# FPGA_programmer.net
KiCad netlist of a schematic drawn in Altium Designer
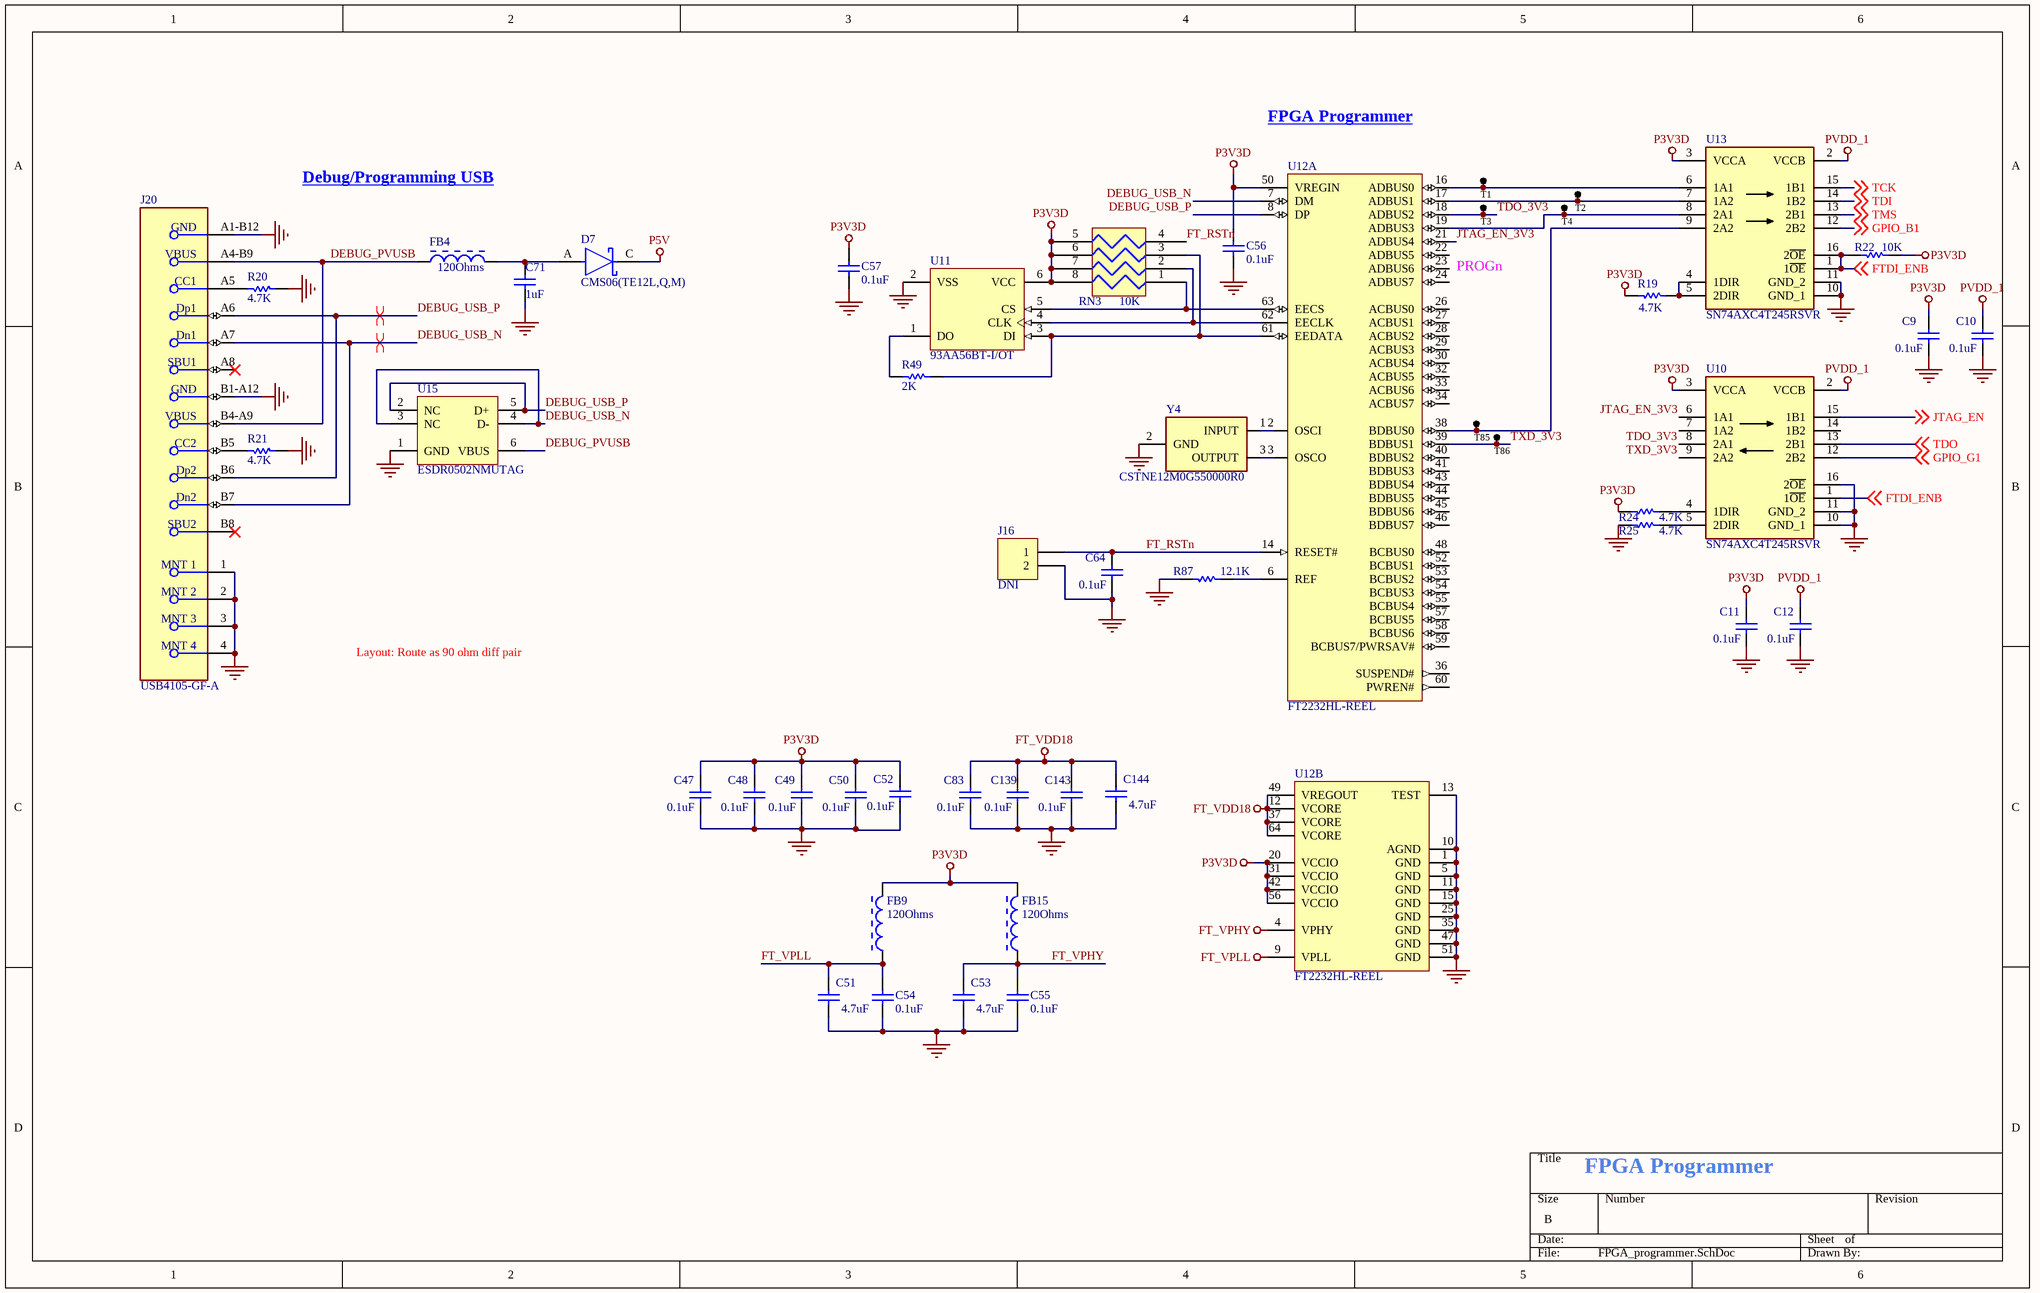
[diagram p0: FPGA_programmer.SchDoc]

(export (version "E")
  (design (tool "Eeschema 10.0.6"))
  (components
    (comp (ref "C9")
      (value "0.1uF")
      (footprint "CAPC1005X55USR")
      (description "CAP CER 0.1UF 16V X7R 0402")
      (fields
        (field (name "MANUFACTURER PART NUMBER") "CGA2B1X7R1C104K050BC")
        (field (name "MANUFACTURER") "TDK Corporation")
      )
      (libsource (lib "NX Module baseboard") (part "CAP CER 0.1UF 16V X7R 0402"))
    )
    (comp (ref "C10")
      (value "0.1uF")
      (footprint "CAPC1005X55USR")
      (description "CAP CER 0.1UF 16V X7R 0402")
      (fields
        (field (name "MANUFACTURER PART NUMBER") "CGA2B1X7R1C104K050BC")
        (field (name "MANUFACTURER") "TDK Corporation")
      )
      (libsource (lib "NX Module baseboard") (part "CAP CER 0.1UF 16V X7R 0402"))
    )
    (comp (ref "C11")
      (value "0.1uF")
      (footprint "CAPC1005X55USR")
      (description "CAP CER 0.1UF 16V X7R 0402")
      (fields
        (field (name "MANUFACTURER PART NUMBER") "CGA2B1X7R1C104K050BC")
        (field (name "MANUFACTURER") "TDK Corporation")
      )
      (libsource (lib "NX Module baseboard") (part "CAP CER 0.1UF 16V X7R 0402"))
    )
    (comp (ref "C12")
      (value "0.1uF")
      (footprint "CAPC1005X55USR")
      (description "CAP CER 0.1UF 16V X7R 0402")
      (fields
        (field (name "MANUFACTURER PART NUMBER") "CGA2B1X7R1C104K050BC")
        (field (name "MANUFACTURER") "TDK Corporation")
      )
      (libsource (lib "NX Module baseboard") (part "CAP CER 0.1UF 16V X7R 0402"))
    )
    (comp (ref "C47")
      (value "0.1uF")
      (footprint "CAPC1005X55USR")
      (description "CAP CER 0.1UF 16V X7R 0402")
      (fields
        (field (name "MANUFACTURER PART NUMBER") "CGA2B1X7R1C104K050BC")
        (field (name "MANUFACTURER") "TDK Corporation")
      )
      (libsource (lib "NX Module baseboard") (part "CAP CER 0.1UF 16V X7R 0402"))
    )
    (comp (ref "C48")
      (value "0.1uF")
      (footprint "CAPC1005X55USR")
      (description "CAP CER 0.1UF 16V X7R 0402")
      (fields
        (field (name "MANUFACTURER PART NUMBER") "CGA2B1X7R1C104K050BC")
        (field (name "MANUFACTURER") "TDK Corporation")
      )
      (libsource (lib "NX Module baseboard") (part "CAP CER 0.1UF 16V X7R 0402"))
    )
    (comp (ref "C49")
      (value "0.1uF")
      (footprint "CAPC1005X55USR")
      (description "CAP CER 0.1UF 16V X7R 0402")
      (fields
        (field (name "MANUFACTURER PART NUMBER") "CGA2B1X7R1C104K050BC")
        (field (name "MANUFACTURER") "TDK Corporation")
      )
      (libsource (lib "NX Module baseboard") (part "CAP CER 0.1UF 16V X7R 0402"))
    )
    (comp (ref "C50")
      (value "0.1uF")
      (footprint "CAPC1005X55USR")
      (description "CAP CER 0.1UF 16V X7R 0402")
      (fields
        (field (name "MANUFACTURER PART NUMBER") "CGA2B1X7R1C104K050BC")
        (field (name "MANUFACTURER") "TDK Corporation")
      )
      (libsource (lib "NX Module baseboard") (part "CAP CER 0.1UF 16V X7R 0402"))
    )
    (comp (ref "C51")
      (value "4.7uF")
      (footprint "CAPC1005X55USR")
      (description "CAP CER 4.7UF 10V X5R 0402")
      (fields
        (field (name "MANUFACTURER PART NUMBER") "C1005X5R1A475M050BC")
        (field (name "MANUFACTURER") "TDK Corporation")
      )
      (libsource (lib "NX Module baseboard") (part "CAP CER 4.7UF 10V X5R 0402"))
    )
    (comp (ref "C52")
      (value "0.1uF")
      (footprint "CAPC1005X55USR")
      (description "CAP CER 0.1UF 16V X7R 0402")
      (fields
        (field (name "MANUFACTURER PART NUMBER") "CGA2B1X7R1C104K050BC")
        (field (name "MANUFACTURER") "TDK Corporation")
      )
      (libsource (lib "NX Module baseboard") (part "CAP CER 0.1UF 16V X7R 0402"))
    )
    (comp (ref "C53")
      (value "4.7uF")
      (footprint "CAPC1005X55USR")
      (description "CAP CER 4.7UF 10V X5R 0402")
      (fields
        (field (name "MANUFACTURER PART NUMBER") "C1005X5R1A475M050BC")
        (field (name "MANUFACTURER") "TDK Corporation")
      )
      (libsource (lib "NX Module baseboard") (part "CAP CER 4.7UF 10V X5R 0402"))
    )
    (comp (ref "C54")
      (value "0.1uF")
      (footprint "CAPC1005X55USR")
      (description "CAP CER 0.1UF 16V X7R 0402")
      (fields
        (field (name "MANUFACTURER PART NUMBER") "CGA2B1X7R1C104K050BC")
        (field (name "MANUFACTURER") "TDK Corporation")
      )
      (libsource (lib "NX Module baseboard") (part "CAP CER 0.1UF 16V X7R 0402"))
    )
    (comp (ref "C55")
      (value "0.1uF")
      (footprint "CAPC1005X55USR")
      (description "CAP CER 0.1UF 16V X7R 0402")
      (fields
        (field (name "MANUFACTURER PART NUMBER") "CGA2B1X7R1C104K050BC")
        (field (name "MANUFACTURER") "TDK Corporation")
      )
      (libsource (lib "NX Module baseboard") (part "CAP CER 0.1UF 16V X7R 0402"))
    )
    (comp (ref "C56")
      (value "0.1uF")
      (footprint "CAPC1005X55USR")
      (description "CAP CER 0.1UF 16V X7R 0402")
      (fields
        (field (name "MANUFACTURER PART NUMBER") "CGA2B1X7R1C104K050BC")
        (field (name "MANUFACTURER") "TDK Corporation")
      )
      (libsource (lib "NX Module baseboard") (part "CAP CER 0.1UF 16V X7R 0402"))
    )
    (comp (ref "C57")
      (value "0.1uF")
      (footprint "CAPC1005X55USR")
      (description "CAP CER 0.1UF 16V X7R 0402")
      (fields
        (field (name "MANUFACTURER PART NUMBER") "CGA2B1X7R1C104K050BC")
        (field (name "MANUFACTURER") "TDK Corporation")
      )
      (libsource (lib "NX Module baseboard") (part "CAP CER 0.1UF 16V X7R 0402"))
    )
    (comp (ref "C64")
      (value "0.1uF")
      (footprint "CAPC1005X55USR")
      (description "CAP CER 0.1UF 16V X7R 0402")
      (fields
        (field (name "MANUFACTURER PART NUMBER") "CGA2B1X7R1C104K050BC")
        (field (name "MANUFACTURER") "TDK Corporation")
      )
      (libsource (lib "NX Module baseboard") (part "CAP CER 0.1UF 16V X7R 0402"))
    )
    (comp (ref "C71")
      (value "1uF")
      (footprint "CAPC1005X55USR")
      (description "CAP CER 1UF 25V X5R 0402")
      (fields
        (field (name "MANUFACTURER PART NUMBER") "GRM155R61E105MA12D")
        (field (name "MANUFACTURER") "Murata Electronics")
      )
      (libsource (lib "Tiger_Ti180") (part "CAP CER 1UF 25V X5R 0402"))
    )
    (comp (ref "C83")
      (value "0.1uF")
      (footprint "CAPC1005X55USR")
      (description "CAP CER 0.1UF 16V X7R 0402")
      (fields
        (field (name "MANUFACTURER PART NUMBER") "CGA2B1X7R1C104K050BC")
        (field (name "MANUFACTURER") "TDK Corporation")
      )
      (libsource (lib "NX Module baseboard") (part "CAP CER 0.1UF 16V X7R 0402"))
    )
    (comp (ref "C139")
      (value "0.1uF")
      (footprint "CAPC1005X55USR")
      (description "CAP CER 0.1UF 16V X7R 0402")
      (fields
        (field (name "MANUFACTURER PART NUMBER") "CGA2B1X7R1C104K050BC")
        (field (name "MANUFACTURER") "TDK Corporation")
      )
      (libsource (lib "NX Module baseboard") (part "CAP CER 0.1UF 16V X7R 0402"))
    )
    (comp (ref "C143")
      (value "0.1uF")
      (footprint "CAPC1005X55USR")
      (description "CAP CER 0.1UF 16V X7R 0402")
      (fields
        (field (name "MANUFACTURER PART NUMBER") "CGA2B1X7R1C104K050BC")
        (field (name "MANUFACTURER") "TDK Corporation")
      )
      (libsource (lib "NX Module baseboard") (part "CAP CER 0.1UF 16V X7R 0402"))
    )
    (comp (ref "C144")
      (value "4.7uF")
      (footprint "CAPC1005X55USR")
      (description "CAP CER 4.7UF 10V X5R 0402")
      (fields
        (field (name "MANUFACTURER PART NUMBER") "C1005X5R1A475M050BC")
        (field (name "MANUFACTURER") "TDK Corporation")
      )
      (libsource (lib "NX Module baseboard") (part "CAP CER 4.7UF 10V X5R 0402"))
    )
    (comp (ref "D7")
      (value "CMS06(TE12L,Q,M)")
      (footprint "SOD-128")
      (description "Rectifier Diode Schottky 30V 2A 2-Pin M-FLAT T/R")
      (fields (field (name "MANUFACTURER") "Toshiba"))
      (libsource (lib "Tiger_Ti180") (part "D_CMS06(TE12L,Q,M)"))
    )
    (comp (ref "FB4")
      (value "120Ohms")
      (footprint "0402_FB")
      (description "FERRITE BEAD 120 OHM 0402 1LN")
      (fields
        (field (name "MANUFACTURER PART NUMBER") "BLM15AG121SN1D")
        (field (name "MANUFACTURER") "Murata Electronics")
      )
      (libsource (lib "AiC") (part "FERRITE BEAD 120 OHM 0402 1LN"))
    )
    (comp (ref "FB9")
      (value "120Ohms")
      (footprint "0402_FB")
      (description "FERRITE BEAD 120 OHM 0402 1LN")
      (fields
        (field (name "MANUFACTURER PART NUMBER") "BLM15AG121SN1D")
        (field (name "MANUFACTURER") "Murata Electronics")
      )
      (libsource (lib "AiC") (part "FERRITE BEAD 120 OHM 0402 1LN"))
    )
    (comp (ref "FB15")
      (value "120Ohms")
      (footprint "0402_FB")
      (description "FERRITE BEAD 120 OHM 0402 1LN")
      (fields
        (field (name "MANUFACTURER PART NUMBER") "BLM15AG121SN1D")
        (field (name "MANUFACTURER") "Murata Electronics")
      )
      (libsource (lib "AiC") (part "FERRITE BEAD 120 OHM 0402 1LN"))
    )
    (comp (ref "J16")
      (value "Header 2X1_2.54MM")
      (footprint "HDR2X1_MALE_2.54MM")
      (description "Conn Header Vert 2POS 2.54MM")
      (fields
        (field (name "MANUFACTURER PART NUMBER") "PRPC002SAAN-RC")
        (field (name "MANUFACTURER") "Sullins")
        (field (name "CONTENT") "DNI")
      )
      (libsource (lib "NX Module baseboard") (part "Header 2X1_2.54MM"))
    )
    (comp (ref "J20")
      (value "USB4105-GF-A")
      (footprint "USB4105_GCT")
      (description "Conn USB 2.0 Type C RCP 24 POS 0.3mm/0.5mm Solder RA SMD 24 Terminal 1 Port T/R")
      (fields (field (name "MANUFACTURER") "Global Connector Technology"))
      (libsource (lib "Tiger_Ti180") (part "CONN RCP USB2.0 TYP C 24P SMD RA"))
    )
    (comp (ref "R19")
      (value "4.7K")
      (footprint "RESC1005X40USR")
      (description "RES SMD 4.7K OHM 1% 1/16W 0402")
      (fields
        (field (name "MANUFACTURER") "Stackpole Electronics Inc")
        (field (name "MANUFACTURER PART NUMBER") "RMCF0402FT4K70")
      )
      (libsource (lib "Tiger_Ti180") (part "RES 4.7K OHM 1% 1/16W 0402"))
    )
    (comp (ref "R20")
      (value "4.7K")
      (footprint "RESC1005X40USR")
      (description "RES SMD 4.7K OHM 1% 1/16W 0402")
      (fields
        (field (name "MANUFACTURER") "Stackpole Electronics Inc")
        (field (name "MANUFACTURER PART NUMBER") "RMCF0402FT4K70")
      )
      (libsource (lib "Tiger_Ti180") (part "RES 4.7K OHM 1% 1/16W 0402"))
    )
    (comp (ref "R21")
      (value "4.7K")
      (footprint "RESC1005X40USR")
      (description "RES SMD 4.7K OHM 1% 1/16W 0402")
      (fields
        (field (name "MANUFACTURER") "Stackpole Electronics Inc")
        (field (name "MANUFACTURER PART NUMBER") "RMCF0402FT4K70")
      )
      (libsource (lib "Tiger_Ti180") (part "RES 4.7K OHM 1% 1/16W 0402"))
    )
    (comp (ref "R22")
      (value "10K")
      (footprint "RESC1005X40USR")
      (description "RES SMD 10K OHM 1% 1/16W 0402")
      (fields
        (field (name "MANUFACTURER") "Samsung Electro-Mechanics")
        (field (name "MANUFACTURER PART NUMBER") "RC1005F103CS")
      )
      (libsource (lib "NX Module baseboard") (part "RES SMD 10K OHM 1% 1/16W 0402"))
    )
    (comp (ref "R24")
      (value "4.7K")
      (footprint "RESC1005X40USR")
      (description "RES SMD 4.7K OHM 1% 1/16W 0402")
      (fields
        (field (name "MANUFACTURER") "Stackpole Electronics Inc")
        (field (name "MANUFACTURER PART NUMBER") "RMCF0402FT4K70")
      )
      (libsource (lib "Tiger_Ti180") (part "RES 4.7K OHM 1% 1/16W 0402"))
    )
    (comp (ref "R25")
      (value "4.7K")
      (footprint "RESC1005X40USR")
      (description "RES SMD 4.7K OHM 1% 1/16W 0402")
      (fields
        (field (name "MANUFACTURER") "Stackpole Electronics Inc")
        (field (name "MANUFACTURER PART NUMBER") "RMCF0402FT4K70")
      )
      (libsource (lib "Tiger_Ti180") (part "RES 4.7K OHM 1% 1/16W 0402"))
    )
    (comp (ref "R49")
      (value "2K")
      (footprint "RESC1005X40USR")
      (description "RES 2K OHM 1% 1/16W 0402")
      (fields
        (field (name "MANUFACTURER") "YAGEO")
        (field (name "MANUFACTURER PART NUMBER") "RC0402FR-072KL")
      )
      (libsource (lib "AiC") (part "RES 2K OHM 1% 1/16W 0402"))
    )
    (comp (ref "R87")
      (value "12.1K")
      (footprint "RESC1005X40USR")
      (description "RES 12.1K OHM 1% 1/16W 0402")
      (fields
        (field (name "MANUFACTURER") "Yageo")
        (field (name "MANUFACTURER PART NUMBER") "RC0402FR-0712K1L")
      )
      (libsource (lib "AiC") (part "RES 12.1K OHM 1% 1/16W 0402"))
    )
    (comp (ref "RN3")
      (value "10K")
      (footprint "RESCAXS50P100X200X45-8NA")
      (description "Res Thick Film Array 10K Ohm 5% ±200ppm/°C ISOL 8-Pin 0804(4 X 0402) Convex SMD Automotive T/R")
      (fields
        (field (name "MANUFACTURER") "Panasonic")
        (field (name "MANUFACTURER PART NUMBER") "EXB-28V103JX")
      )
      (libsource (lib "NX Module") (part "RES ARRAY 4 RES 47K OHM 0804"))
    )
    (comp (ref "T1")
      (value "TP_S")
      (footprint "TP 1mm")
      (description "test point")
      (libsource (lib "AiC") (part "TP_S"))
    )
    (comp (ref "T2")
      (value "TP_S")
      (footprint "TP 1mm")
      (description "test point")
      (libsource (lib "AiC") (part "TP_S"))
    )
    (comp (ref "T3")
      (value "TP_S")
      (footprint "TP 1mm")
      (description "test point")
      (libsource (lib "AiC") (part "TP_S"))
    )
    (comp (ref "T4")
      (value "TP_S")
      (footprint "TP 1mm")
      (description "test point")
      (libsource (lib "AiC") (part "TP_S"))
    )
    (comp (ref "T85")
      (value "TP_S")
      (footprint "TP 1mm")
      (description "test point")
      (libsource (lib "AiC") (part "TP_S"))
    )
    (comp (ref "T86")
      (value "TP_S")
      (footprint "TP 1mm")
      (description "test point")
      (libsource (lib "AiC") (part "TP_S"))
    )
    (comp (ref "U10")
      (value "SN74AXC4T245RSVR")
      (footprint "QFN40P260X180X55-16N")
      (description "4-Bit Bus Transceiver with Configurable Voltage Translation and Tri-State Outputs 16-Pin UQFN")
      (fields (field (name "MANUFACTURER") "Texas Instruments"))
      (libsource (lib "NX Module baseboard") (part "SN74AXC4T245RSVR"))
    )
    (comp (ref "U11")
      (value "93AA56BT-I/OT")
      (footprint "SOT23-6")
      (description "IC EEPROM 2KBIT SPI 2MHZ SOT23-6")
      (fields (field (name "MANUFACTURER") "Microchip Technology"))
      (libsource (lib "AiC") (part "93AA56BT-I/OT"))
    )
    (comp (ref "U12")
      (value "FT2232HL-REEL")
      (footprint "QFP50P1200X1200X160-64N")
      (description "IC USB HS DUAL UART/FIFO 64-LQFP")
      (fields (field (name "MANUFACTURER") "FTDI"))
      (libsource (lib "AiC") (part "FT2232HL-REEL"))
    )
    (comp (ref "U13")
      (value "SN74AXC4T245RSVR")
      (footprint "QFN40P260X180X55-16N")
      (description "4-Bit Bus Transceiver with Configurable Voltage Translation and Tri-State Outputs 16-Pin UQFN")
      (fields (field (name "MANUFACTURER") "Texas Instruments"))
      (libsource (lib "NX Module baseboard") (part "SN74AXC4T245RSVR"))
    )
    (comp (ref "U15")
      (value "ESDR0502NMUTAG")
      (footprint "ONSC-UDFN-6-517AA-01_V")
      (description "TVS DIODE 5.5VWM 6UDFN")
      (fields (field (name "MANUFACTURER") "ON Semiconductor"))
      (libsource (lib "Tiger_Ti180") (part "ONSC-ESDR0502N-UDFN-6-517AA-01"))
    )
    (comp (ref "Y4")
      (value "CSTNE12M0G550000R0")
      (footprint "OSC_CSTNE12M0G550000R0")
      (description "CERAMIC RES 12.0000MHZ 33PF SMD")
      (fields (field (name "MANUFACTURER") "Murata Electronics"))
      (libsource (lib "AiC") (part "CSTNE12M0G550000R0"))
    )
  )
  (nets
    (net (code "1") (name "/DEBUG_PVUSB") (class "Default")
      (node (ref "FB4") (pin "1") (pinfunction "1_1") (pintype "passive"))
      (node (ref "J20") (pin "A4-B9") (pinfunction "VBUS_A4-B9") (pintype "power_in"))
      (node (ref "J20") (pin "B4-A9") (pinfunction "VBUS_B4-A9") (pintype "bidirectional"))
      (node (ref "U15") (pin "6") (pinfunction "VBUS_6") (pintype "power_in"))
    )
    (net (code "2") (name "/DEBUG_USB_N") (class "Default")
      (node (ref "J20") (pin "A7") (pinfunction "Dn1_A7") (pintype "bidirectional"))
      (node (ref "J20") (pin "B7") (pinfunction "Dn2_B7") (pintype "bidirectional"))
      (node (ref "U12") (pin "7") (pinfunction "DM_7") (pintype "bidirectional"))
      (node (ref "U15") (pin "3") (pinfunction "NC_3") (pintype "passive"))
      (node (ref "U15") (pin "4") (pinfunction "D-_4") (pintype "passive"))
    )
    (net (code "3") (name "/DEBUG_USB_P") (class "Default")
      (node (ref "J20") (pin "A6") (pinfunction "Dp1_A6") (pintype "bidirectional"))
      (node (ref "J20") (pin "B6") (pinfunction "Dp2_B6") (pintype "bidirectional"))
      (node (ref "U12") (pin "8") (pinfunction "DP_8") (pintype "bidirectional"))
      (node (ref "U15") (pin "2") (pinfunction "NC_2") (pintype "passive"))
      (node (ref "U15") (pin "5") (pinfunction "D+_5") (pintype "passive"))
    )
    (net (code "4") (name "/FT_RSTn") (class "Default")
      (node (ref "C64") (pin "2") (pinfunction "2_2") (pintype "passive"))
      (node (ref "J16") (pin "1") (pinfunction "1_1") (pintype "passive"))
      (node (ref "RN3") (pin "4") (pintype "passive"))
      (node (ref "U12") (pin "14") (pinfunction "RESET#_14") (pintype "input"))
    )
    (net (code "5") (name "/JTAG_EN_3V3") (class "Default")
      (node (ref "U10") (pin "6") (pinfunction "1A1_6") (pintype "passive"))
      (node (ref "U12") (pin "21") (pinfunction "ADBUS4_21") (pintype "bidirectional"))
    )
    (net (code "6") (name "/TDO_3V3") (class "Default")
      (node (ref "T3") (pin "1") (pintype "passive"))
      (node (ref "U10") (pin "8") (pinfunction "2A1_8") (pintype "passive"))
      (node (ref "U12") (pin "18") (pinfunction "ADBUS2_18") (pintype "bidirectional"))
    )
    (net (code "7") (name "/TXD_3V3") (class "Default")
      (node (ref "T86") (pin "1") (pintype "passive"))
      (node (ref "U10") (pin "9") (pinfunction "2A2_9") (pintype "passive"))
      (node (ref "U12") (pin "39") (pinfunction "BDBUS1_39") (pintype "bidirectional"))
    )
    (net (code "8") (name "FTDI_ENB") (class "Default")
      (node (ref "R22") (pin "1") (pinfunction "1_1") (pintype "passive"))
      (node (ref "U10") (pin "1") (pinfunction "1~{OE}_1") (pintype "passive"))
      (node (ref "U13") (pin "1") (pinfunction "1~{OE}_1") (pintype "passive"))
      (node (ref "U13") (pin "16") (pinfunction "2~{OE}_16") (pintype "passive"))
    )
    (net (code "9") (name "FT_VDD18") (class "Default")
      (node (ref "C139") (pin "2") (pinfunction "2_2") (pintype "passive"))
      (node (ref "C143") (pin "2") (pinfunction "2_2") (pintype "passive"))
      (node (ref "C144") (pin "2") (pinfunction "2_2") (pintype "passive"))
      (node (ref "C83") (pin "2") (pinfunction "2_2") (pintype "passive"))
      (node (ref "U12") (pin "12") (pinfunction "VCORE_12") (pintype "power_in"))
      (node (ref "U12") (pin "37") (pinfunction "VCORE_37") (pintype "power_in"))
      (node (ref "U12") (pin "49") (pinfunction "VREGOUT_49") (pintype "power_in"))
      (node (ref "U12") (pin "64") (pinfunction "VCORE_64") (pintype "power_in"))
    )
    (net (code "10") (name "FT_VPHY") (class "Default")
      (node (ref "C53") (pin "2") (pinfunction "2_2") (pintype "passive"))
      (node (ref "C55") (pin "2") (pinfunction "2_2") (pintype "passive"))
      (node (ref "FB15") (pin "1") (pinfunction "1_1") (pintype "passive"))
      (node (ref "U12") (pin "4") (pinfunction "VPHY_4") (pintype "power_in"))
    )
    (net (code "11") (name "FT_VPLL") (class "Default")
      (node (ref "C51") (pin "2") (pinfunction "2_2") (pintype "passive"))
      (node (ref "C54") (pin "2") (pinfunction "2_2") (pintype "passive"))
      (node (ref "FB9") (pin "1") (pinfunction "1_1") (pintype "passive"))
      (node (ref "U12") (pin "9") (pinfunction "VPLL_9") (pintype "power_in"))
    )
    (net (code "12") (name "GND") (class "Default")
      (node (ref "C10") (pin "1") (pinfunction "1_1") (pintype "passive"))
      (node (ref "C11") (pin "1") (pinfunction "1_1") (pintype "passive"))
      (node (ref "C12") (pin "1") (pinfunction "1_1") (pintype "passive"))
      (node (ref "C139") (pin "1") (pinfunction "1_1") (pintype "passive"))
      (node (ref "C143") (pin "1") (pinfunction "1_1") (pintype "passive"))
      (node (ref "C144") (pin "1") (pinfunction "1_1") (pintype "passive"))
      (node (ref "C47") (pin "1") (pinfunction "1_1") (pintype "passive"))
      (node (ref "C48") (pin "1") (pinfunction "1_1") (pintype "passive"))
      (node (ref "C49") (pin "1") (pinfunction "1_1") (pintype "passive"))
      (node (ref "C50") (pin "1") (pinfunction "1_1") (pintype "passive"))
      (node (ref "C51") (pin "1") (pinfunction "1_1") (pintype "passive"))
      (node (ref "C52") (pin "1") (pinfunction "1_1") (pintype "passive"))
      (node (ref "C53") (pin "1") (pinfunction "1_1") (pintype "passive"))
      (node (ref "C54") (pin "1") (pinfunction "1_1") (pintype "passive"))
      (node (ref "C55") (pin "1") (pinfunction "1_1") (pintype "passive"))
      (node (ref "C56") (pin "1") (pinfunction "1_1") (pintype "passive"))
      (node (ref "C57") (pin "1") (pinfunction "1_1") (pintype "passive"))
      (node (ref "C64") (pin "1") (pinfunction "1_1") (pintype "passive"))
      (node (ref "C71") (pin "1") (pinfunction "1_1") (pintype "passive"))
      (node (ref "C83") (pin "1") (pinfunction "1_1") (pintype "passive"))
      (node (ref "C9") (pin "1") (pinfunction "1_1") (pintype "passive"))
      (node (ref "J16") (pin "2") (pinfunction "2_2") (pintype "passive"))
      (node (ref "J20") (pin "1") (pinfunction "MNT_1_1") (pintype "power_in"))
      (node (ref "J20") (pin "2") (pinfunction "MNT_2_2") (pintype "power_in"))
      (node (ref "J20") (pin "3") (pinfunction "MNT_3_3") (pintype "power_in"))
      (node (ref "J20") (pin "4") (pinfunction "MNT_4_4") (pintype "power_in"))
      (node (ref "J20") (pin "A1-B12") (pinfunction "GND_A1-B12") (pintype "power_in"))
      (node (ref "J20") (pin "B1-A12") (pinfunction "GND_B1-A12") (pintype "bidirectional"))
      (node (ref "R20") (pin "1") (pinfunction "1_1") (pintype "passive"))
      (node (ref "R21") (pin "1") (pinfunction "1_1") (pintype "passive"))
      (node (ref "R25") (pin "2") (pinfunction "2_2") (pintype "passive"))
      (node (ref "R87") (pin "1") (pinfunction "1_1") (pintype "passive"))
      (node (ref "U10") (pin "10") (pinfunction "GND_1_10") (pintype "passive"))
      (node (ref "U10") (pin "11") (pinfunction "GND_2_11") (pintype "passive"))
      (node (ref "U10") (pin "16") (pinfunction "2~{OE}_16") (pintype "passive"))
      (node (ref "U11") (pin "2") (pinfunction "VSS_2") (pintype "power_in"))
      (node (ref "U12") (pin "1") (pinfunction "GND_1") (pintype "power_in"))
      (node (ref "U12") (pin "10") (pinfunction "AGND_10") (pintype "power_in"))
      (node (ref "U12") (pin "11") (pinfunction "GND_11") (pintype "power_in"))
      (node (ref "U12") (pin "13") (pinfunction "TEST_13") (pintype "passive"))
      (node (ref "U12") (pin "15") (pinfunction "GND_15") (pintype "power_in"))
      (node (ref "U12") (pin "25") (pinfunction "GND_25") (pintype "power_in"))
      (node (ref "U12") (pin "35") (pinfunction "GND_35") (pintype "power_in"))
      (node (ref "U12") (pin "47") (pinfunction "GND_47") (pintype "power_in"))
      (node (ref "U12") (pin "5") (pinfunction "GND_5") (pintype "power_in"))
      (node (ref "U12") (pin "51") (pinfunction "GND_51") (pintype "power_in"))
      (node (ref "U13") (pin "10") (pinfunction "GND_1_10") (pintype "passive"))
      (node (ref "U13") (pin "11") (pinfunction "GND_2_11") (pintype "passive"))
      (node (ref "U15") (pin "1") (pinfunction "GND_1") (pintype "power_in"))
      (node (ref "Y4") (pin "2") (pinfunction "GND_2") (pintype "passive"))
    )
    (net (code "13") (name "GPIO_B1") (class "Default")
      (node (ref "U13") (pin "12") (pinfunction "2B2_12") (pintype "passive"))
    )
    (net (code "14") (name "GPIO_G1") (class "Default")
      (node (ref "U10") (pin "12") (pinfunction "2B2_12") (pintype "passive"))
    )
    (net (code "15") (name "JTAG_EN") (class "Default")
      (node (ref "U10") (pin "15") (pinfunction "1B1_15") (pintype "passive"))
    )
    (net (code "16") (name "Net-(C71-Pad2)") (class "Default")
      (node (ref "C71") (pin "2") (pinfunction "2_2") (pintype "passive"))
      (node (ref "D7") (pin "A") (pinfunction "A_A") (pintype "passive"))
      (node (ref "FB4") (pin "2") (pinfunction "2_2") (pintype "passive"))
    )
    (net (code "17") (name "Net-(J20-CC1)") (class "Default")
      (node (ref "J20") (pin "A5") (pinfunction "CC1_A5") (pintype "power_in"))
      (node (ref "R20") (pin "2") (pinfunction "2_2") (pintype "passive"))
    )
    (net (code "18") (name "Net-(J20-CC2)") (class "Default")
      (node (ref "J20") (pin "B5") (pinfunction "CC2_B5") (pintype "bidirectional"))
      (node (ref "R21") (pin "2") (pinfunction "2_2") (pintype "passive"))
    )
    (net (code "19") (name "Net-(U10-1DIR)") (class "Default")
      (node (ref "R24") (pin "1") (pinfunction "1_1") (pintype "passive"))
      (node (ref "U10") (pin "4") (pinfunction "1DIR_4") (pintype "passive"))
    )
    (net (code "20") (name "Net-(U10-2DIR)") (class "Default")
      (node (ref "R25") (pin "1") (pinfunction "1_1") (pintype "passive"))
      (node (ref "U10") (pin "5") (pinfunction "2DIR_5") (pintype "passive"))
    )
    (net (code "21") (name "Net-(U11-CLK)") (class "Default")
      (node (ref "RN3") (pin "2") (pintype "passive"))
      (node (ref "U11") (pin "4") (pinfunction "CLK_4") (pintype "input"))
      (node (ref "U12") (pin "62") (pinfunction "EECLK_62") (pintype "tri_state"))
    )
    (net (code "22") (name "Net-(U11-CS)") (class "Default")
      (node (ref "RN3") (pin "1") (pintype "passive"))
      (node (ref "U11") (pin "5") (pinfunction "CS_5") (pintype "input"))
      (node (ref "U12") (pin "63") (pinfunction "EECS_63") (pintype "bidirectional"))
    )
    (net (code "23") (name "Net-(U11-DI)") (class "Default")
      (node (ref "R49") (pin "1") (pinfunction "1_1") (pintype "passive"))
      (node (ref "RN3") (pin "3") (pintype "passive"))
      (node (ref "U11") (pin "3") (pinfunction "DI_3") (pintype "input"))
      (node (ref "U12") (pin "61") (pinfunction "EEDATA_61") (pintype "bidirectional"))
    )
    (net (code "24") (name "Net-(U11-DO)") (class "Default")
      (node (ref "R49") (pin "2") (pinfunction "2_2") (pintype "passive"))
      (node (ref "U11") (pin "1") (pinfunction "DO_1") (pintype "tri_state"))
    )
    (net (code "25") (name "Net-(U12A-ADBUS0)") (class "Default")
      (node (ref "T1") (pin "1") (pintype "passive"))
      (node (ref "U12") (pin "16") (pinfunction "ADBUS0_16") (pintype "bidirectional"))
      (node (ref "U13") (pin "6") (pinfunction "1A1_6") (pintype "passive"))
    )
    (net (code "26") (name "Net-(U12A-ADBUS1)") (class "Default")
      (node (ref "T2") (pin "1") (pintype "passive"))
      (node (ref "U12") (pin "17") (pinfunction "ADBUS1_17") (pintype "bidirectional"))
      (node (ref "U13") (pin "7") (pinfunction "1A2_7") (pintype "passive"))
    )
    (net (code "27") (name "Net-(U12A-ADBUS3)") (class "Default")
      (node (ref "T4") (pin "1") (pintype "passive"))
      (node (ref "U12") (pin "19") (pinfunction "ADBUS3_19") (pintype "bidirectional"))
      (node (ref "U13") (pin "8") (pinfunction "2A1_8") (pintype "passive"))
    )
    (net (code "28") (name "Net-(U12A-BDBUS0)") (class "Default")
      (node (ref "T85") (pin "1") (pintype "passive"))
      (node (ref "U12") (pin "38") (pinfunction "BDBUS0_38") (pintype "bidirectional"))
      (node (ref "U13") (pin "9") (pinfunction "2A2_9") (pintype "passive"))
    )
    (net (code "29") (name "Net-(U12A-OSCI)") (class "Default")
      (node (ref "U12") (pin "2") (pinfunction "OSCI_2") (pintype "passive"))
      (node (ref "Y4") (pin "1") (pinfunction "INPUT_1") (pintype "passive"))
    )
    (net (code "30") (name "Net-(U12A-OSCO)") (class "Default")
      (node (ref "U12") (pin "3") (pinfunction "OSCO_3") (pintype "passive"))
      (node (ref "Y4") (pin "3") (pinfunction "OUTPUT_3") (pintype "passive"))
    )
    (net (code "31") (name "Net-(U12A-REF)") (class "Default")
      (node (ref "R87") (pin "2") (pinfunction "2_2") (pintype "passive"))
      (node (ref "U12") (pin "6") (pinfunction "REF_6") (pintype "passive"))
    )
    (net (code "32") (name "Net-(U13-1DIR)") (class "Default")
      (node (ref "R19") (pin "1") (pinfunction "1_1") (pintype "passive"))
      (node (ref "U13") (pin "4") (pinfunction "1DIR_4") (pintype "passive"))
      (node (ref "U13") (pin "5") (pinfunction "2DIR_5") (pintype "passive"))
    )
    (net (code "33") (name "P3V3D") (class "Default")
      (node (ref "C11") (pin "2") (pinfunction "2_2") (pintype "passive"))
      (node (ref "C47") (pin "2") (pinfunction "2_2") (pintype "passive"))
      (node (ref "C48") (pin "2") (pinfunction "2_2") (pintype "passive"))
      (node (ref "C49") (pin "2") (pinfunction "2_2") (pintype "passive"))
      (node (ref "C50") (pin "2") (pinfunction "2_2") (pintype "passive"))
      (node (ref "C52") (pin "2") (pinfunction "2_2") (pintype "passive"))
      (node (ref "C56") (pin "2") (pinfunction "2_2") (pintype "passive"))
      (node (ref "C57") (pin "2") (pinfunction "2_2") (pintype "passive"))
      (node (ref "C9") (pin "2") (pinfunction "2_2") (pintype "passive"))
      (node (ref "FB15") (pin "2") (pinfunction "2_2") (pintype "passive"))
      (node (ref "FB9") (pin "2") (pinfunction "2_2") (pintype "passive"))
      (node (ref "R19") (pin "2") (pinfunction "2_2") (pintype "passive"))
      (node (ref "R22") (pin "2") (pinfunction "2_2") (pintype "passive"))
      (node (ref "R24") (pin "2") (pinfunction "2_2") (pintype "passive"))
      (node (ref "RN3") (pin "5") (pintype "passive"))
      (node (ref "RN3") (pin "6") (pintype "passive"))
      (node (ref "RN3") (pin "7") (pintype "passive"))
      (node (ref "RN3") (pin "8") (pintype "passive"))
      (node (ref "U10") (pin "3") (pinfunction "VCCA_3") (pintype "passive"))
      (node (ref "U11") (pin "6") (pinfunction "VCC_6") (pintype "power_in"))
      (node (ref "U12") (pin "20") (pinfunction "VCCIO_20") (pintype "power_in"))
      (node (ref "U12") (pin "31") (pinfunction "VCCIO_31") (pintype "power_in"))
      (node (ref "U12") (pin "42") (pinfunction "VCCIO_42") (pintype "power_in"))
      (node (ref "U12") (pin "50") (pinfunction "VREGIN_50") (pintype "power_in"))
      (node (ref "U12") (pin "56") (pinfunction "VCCIO_56") (pintype "power_in"))
      (node (ref "U13") (pin "3") (pinfunction "VCCA_3") (pintype "passive"))
    )
    (net (code "34") (name "P5V") (class "Default")
      (node (ref "D7") (pin "C") (pinfunction "C_C") (pintype "passive"))
    )
    (net (code "35") (name "PVDD_1") (class "Default")
      (node (ref "C10") (pin "2") (pinfunction "2_2") (pintype "passive"))
      (node (ref "C12") (pin "2") (pinfunction "2_2") (pintype "passive"))
      (node (ref "U10") (pin "2") (pinfunction "VCCB_2") (pintype "passive"))
      (node (ref "U13") (pin "2") (pinfunction "VCCB_2") (pintype "passive"))
    )
    (net (code "36") (name "TCK") (class "Default")
      (node (ref "U13") (pin "15") (pinfunction "1B1_15") (pintype "passive"))
    )
    (net (code "37") (name "TDI") (class "Default")
      (node (ref "U13") (pin "14") (pinfunction "1B2_14") (pintype "passive"))
    )
    (net (code "38") (name "TDO") (class "Default")
      (node (ref "U10") (pin "13") (pinfunction "2B1_13") (pintype "passive"))
    )
    (net (code "39") (name "TMS") (class "Default")
      (node (ref "U13") (pin "13") (pinfunction "2B1_13") (pintype "passive"))
    )
    (net (code "40") (name "unconnected-(J20-SBU1-PadA8)") (class "Default")
      (node (ref "J20") (pin "A8") (pinfunction "SBU1_A8") (pintype "bidirectional+no_connect"))
    )
    (net (code "41") (name "unconnected-(J20-SBU2-PadB8)") (class "Default")
      (node (ref "J20") (pin "B8") (pinfunction "SBU2_B8") (pintype "power_in+no_connect"))
    )
    (net (code "42") (name "unconnected-(U10-1A2-Pad7)") (class "Default")
      (node (ref "U10") (pin "7") (pinfunction "1A2_7") (pintype "passive"))
    )
    (net (code "43") (name "unconnected-(U10-1B2-Pad14)") (class "Default")
      (node (ref "U10") (pin "14") (pinfunction "1B2_14") (pintype "passive"))
    )
    (net (code "44") (name "unconnected-(U12A-ACBUS0-Pad26)") (class "Default")
      (node (ref "U12") (pin "26") (pinfunction "ACBUS0_26") (pintype "bidirectional"))
    )
    (net (code "45") (name "unconnected-(U12A-ACBUS1-Pad27)") (class "Default")
      (node (ref "U12") (pin "27") (pinfunction "ACBUS1_27") (pintype "bidirectional"))
    )
    (net (code "46") (name "unconnected-(U12A-ACBUS2-Pad28)") (class "Default")
      (node (ref "U12") (pin "28") (pinfunction "ACBUS2_28") (pintype "bidirectional"))
    )
    (net (code "47") (name "unconnected-(U12A-ACBUS3-Pad29)") (class "Default")
      (node (ref "U12") (pin "29") (pinfunction "ACBUS3_29") (pintype "bidirectional"))
    )
    (net (code "48") (name "unconnected-(U12A-ACBUS4-Pad30)") (class "Default")
      (node (ref "U12") (pin "30") (pinfunction "ACBUS4_30") (pintype "bidirectional"))
    )
    (net (code "49") (name "unconnected-(U12A-ACBUS5-Pad32)") (class "Default")
      (node (ref "U12") (pin "32") (pinfunction "ACBUS5_32") (pintype "bidirectional"))
    )
    (net (code "50") (name "unconnected-(U12A-ACBUS6-Pad33)") (class "Default")
      (node (ref "U12") (pin "33") (pinfunction "ACBUS6_33") (pintype "bidirectional"))
    )
    (net (code "51") (name "unconnected-(U12A-ACBUS7-Pad34)") (class "Default")
      (node (ref "U12") (pin "34") (pinfunction "ACBUS7_34") (pintype "bidirectional"))
    )
    (net (code "52") (name "unconnected-(U12A-ADBUS5-Pad22)") (class "Default")
      (node (ref "U12") (pin "22") (pinfunction "ADBUS5_22") (pintype "bidirectional"))
    )
    (net (code "53") (name "unconnected-(U12A-ADBUS6-Pad23)") (class "Default")
      (node (ref "U12") (pin "23") (pinfunction "ADBUS6_23") (pintype "bidirectional"))
    )
    (net (code "54") (name "unconnected-(U12A-ADBUS7-Pad24)") (class "Default")
      (node (ref "U12") (pin "24") (pinfunction "ADBUS7_24") (pintype "bidirectional"))
    )
    (net (code "55") (name "unconnected-(U12A-BCBUS0-Pad48)") (class "Default")
      (node (ref "U12") (pin "48") (pinfunction "BCBUS0_48") (pintype "bidirectional"))
    )
    (net (code "56") (name "unconnected-(U12A-BCBUS1-Pad52)") (class "Default")
      (node (ref "U12") (pin "52") (pinfunction "BCBUS1_52") (pintype "bidirectional"))
    )
    (net (code "57") (name "unconnected-(U12A-BCBUS2-Pad53)") (class "Default")
      (node (ref "U12") (pin "53") (pinfunction "BCBUS2_53") (pintype "bidirectional"))
    )
    (net (code "58") (name "unconnected-(U12A-BCBUS3-Pad54)") (class "Default")
      (node (ref "U12") (pin "54") (pinfunction "BCBUS3_54") (pintype "bidirectional"))
    )
    (net (code "59") (name "unconnected-(U12A-BCBUS4-Pad55)") (class "Default")
      (node (ref "U12") (pin "55") (pinfunction "BCBUS4_55") (pintype "bidirectional"))
    )
    (net (code "60") (name "unconnected-(U12A-BCBUS5-Pad57)") (class "Default")
      (node (ref "U12") (pin "57") (pinfunction "BCBUS5_57") (pintype "bidirectional"))
    )
    (net (code "61") (name "unconnected-(U12A-BCBUS6-Pad58)") (class "Default")
      (node (ref "U12") (pin "58") (pinfunction "BCBUS6_58") (pintype "bidirectional"))
    )
    (net (code "62") (name "unconnected-(U12A-BCBUS7{slash}PWRSAV#-Pad59)") (class "Default")
      (node (ref "U12") (pin "59") (pinfunction "BCBUS7/PWRSAV#_59") (pintype "bidirectional"))
    )
    (net (code "63") (name "unconnected-(U12A-BDBUS2-Pad40)") (class "Default")
      (node (ref "U12") (pin "40") (pinfunction "BDBUS2_40") (pintype "bidirectional"))
    )
    (net (code "64") (name "unconnected-(U12A-BDBUS3-Pad41)") (class "Default")
      (node (ref "U12") (pin "41") (pinfunction "BDBUS3_41") (pintype "bidirectional"))
    )
    (net (code "65") (name "unconnected-(U12A-BDBUS4-Pad43)") (class "Default")
      (node (ref "U12") (pin "43") (pinfunction "BDBUS4_43") (pintype "bidirectional"))
    )
    (net (code "66") (name "unconnected-(U12A-BDBUS5-Pad44)") (class "Default")
      (node (ref "U12") (pin "44") (pinfunction "BDBUS5_44") (pintype "bidirectional"))
    )
    (net (code "67") (name "unconnected-(U12A-BDBUS6-Pad45)") (class "Default")
      (node (ref "U12") (pin "45") (pinfunction "BDBUS6_45") (pintype "bidirectional"))
    )
    (net (code "68") (name "unconnected-(U12A-BDBUS7-Pad46)") (class "Default")
      (node (ref "U12") (pin "46") (pinfunction "BDBUS7_46") (pintype "bidirectional"))
    )
    (net (code "69") (name "unconnected-(U12A-PWREN#-Pad60)") (class "Default")
      (node (ref "U12") (pin "60") (pinfunction "PWREN#_60") (pintype "output"))
    )
    (net (code "70") (name "unconnected-(U12A-SUSPEND#-Pad36)") (class "Default")
      (node (ref "U12") (pin "36") (pinfunction "SUSPEND#_36") (pintype "output"))
    )
  )
)
